# Main.net
KiCad netlist of a schematic drawn in Altium Designer
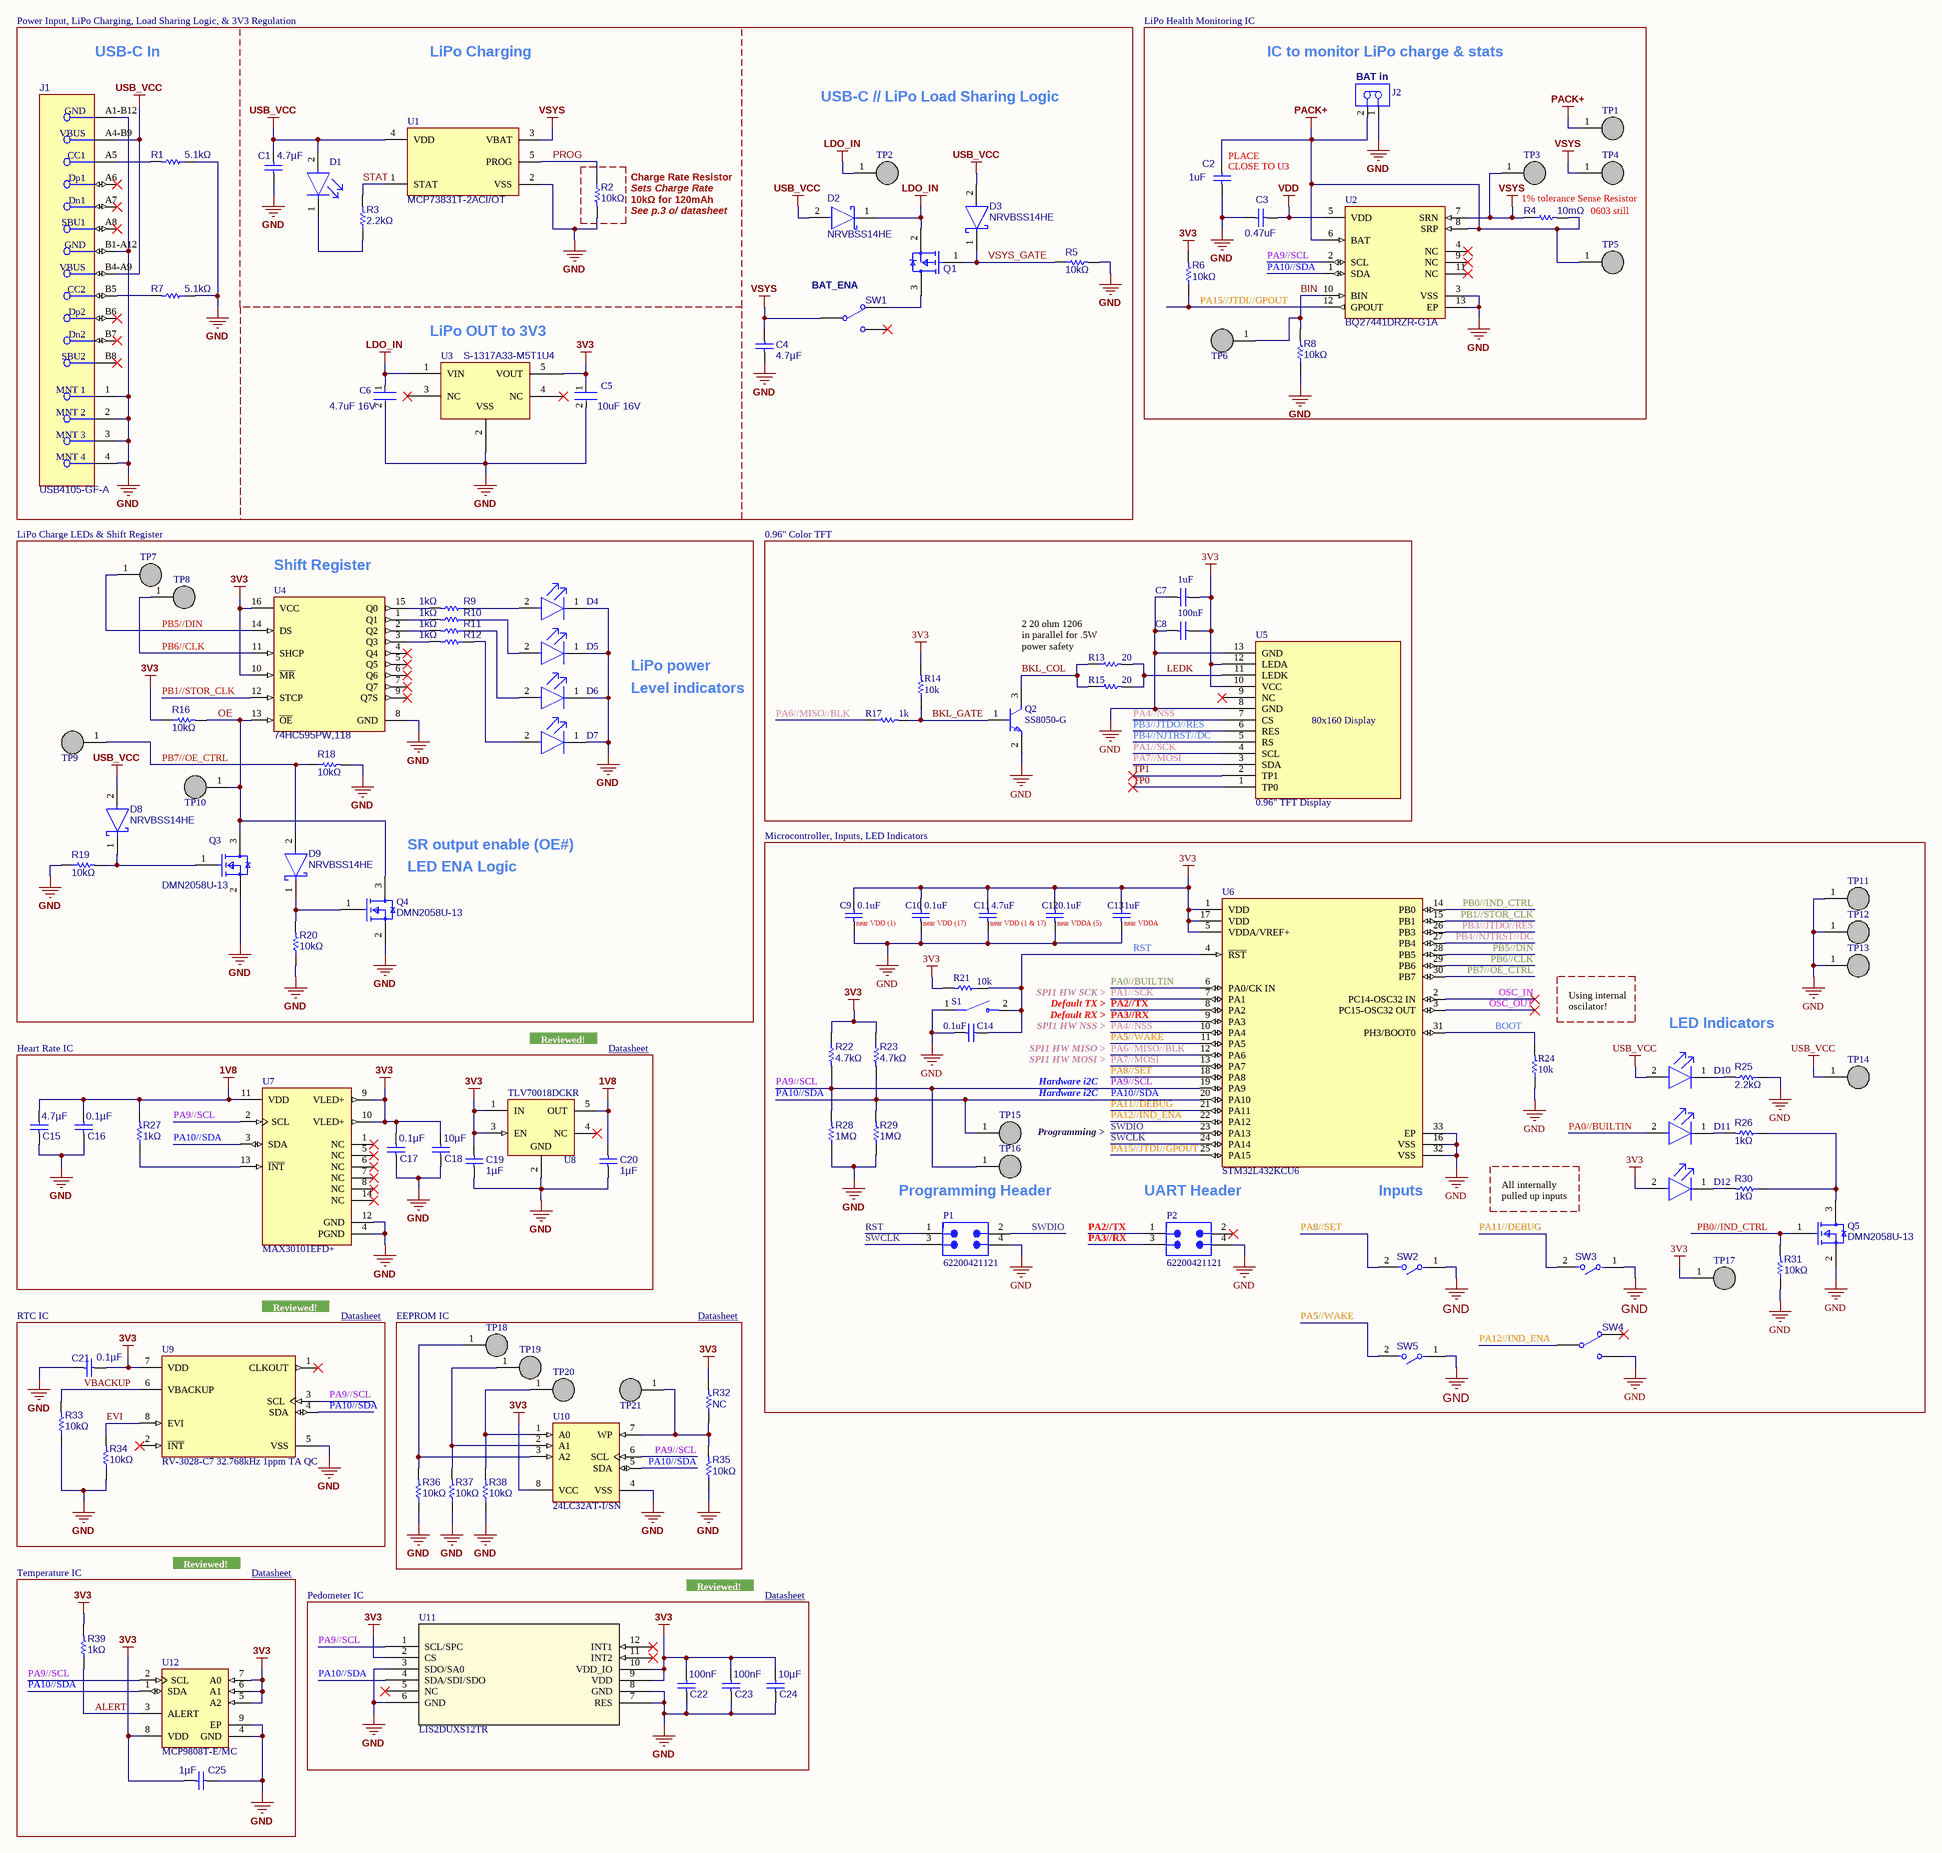
[diagram p0: Main.SchDoc]

(export (version "E")
  (design (tool "Eeschema 10.0.6"))
  (components
    (comp (ref "C1")
      (value "4.7µF")
      (footprint "WCAP-CSGP_0603_L1.6W0.8H0.8_Reflow")
      (libsource (lib "Altium Content Vault") (part "Capacitor_Non-Polarized"))
    )
    (comp (ref "C2")
      (value "1uF")
      (footprint "WCAP-CSGP_0603_L1.6W0.8H0.8_Reflow")
      (libsource (lib "Altium Content Vault") (part "Capacitor_Non-Polarized"))
    )
    (comp (ref "C3")
      (value "0.47uF")
      (footprint "WCAP-CSGP_0603_L1.6W0.8H0.8_Reflow")
      (libsource (lib "Altium Content Vault") (part "Capacitor_Non-Polarized"))
    )
    (comp (ref "C4")
      (value "4.7µF")
      (footprint "WCAP-CSGP_0603_L1.6W0.8H0.8_Reflow")
      (libsource (lib "Altium Content Vault") (part "Capacitor_Non-Polarized"))
    )
    (comp (ref "C5")
      (value "10uF 16V")
      (footprint "FP-CC0603-DC-MFG")
      (description "CM105X5R106K16AT")
      (fields (field (name "TOLERANCE") "10%"))
      (libsource (lib "Altium Content Vault") (part "b4654b650e69147ec39a6b967a45e02"))
    )
    (comp (ref "C6")
      (value "4.7uF 16V")
      (footprint "FP-CC0603-DA-MFG")
      (description "GRM188Z71C475KE21D")
      (fields
        (field (name "MANUFACTURER") "YAGEO")
        (field (name "MANUFACTURER PART NUMBER") "CC0603KRX5R7BB475")
      )
      (libsource (lib "Altium Content Vault") (part "11868f565c42a9108669ba33697ecf6"))
    )
    (comp (ref "C7")
      (value "1uF")
      (footprint "CAPC1608X87X35NL15T15")
      (libsource (lib "Altium Content Vault") (part "CAP"))
    )
    (comp (ref "C8")
      (value "100nF")
      (footprint "CAPC1608X87X35NL15T15")
      (libsource (lib "Altium Content Vault") (part "CAP"))
    )
    (comp (ref "C9")
      (value "0.1uF")
      (footprint "CAPC1608X87X35NL15T15")
      (libsource (lib "Altium Content Vault") (part "CAP"))
    )
    (comp (ref "C10")
      (value "0.1uF")
      (footprint "CAPC1608X87X35NL15T15")
      (libsource (lib "Altium Content Vault") (part "CAP"))
    )
    (comp (ref "C11")
      (value "4.7uF")
      (footprint "CAPC1608X87X35NL15T15")
      (libsource (lib "Altium Content Vault") (part "CAP"))
    )
    (comp (ref "C12")
      (value "0.1uF")
      (footprint "CAPC1608X87X35NL15T15")
      (libsource (lib "Altium Content Vault") (part "CAP"))
    )
    (comp (ref "C13")
      (value "1uF")
      (footprint "CAPC1608X87X35NL15T15")
      (libsource (lib "Altium Content Vault") (part "CAP"))
    )
    (comp (ref "C14")
      (value "0.1uF")
      (footprint "CAPC1608X87X35NL15T15")
      (libsource (lib "Altium Content Vault") (part "CAP"))
    )
    (comp (ref "C15")
      (value "4.7µF")
      (footprint "WCAP-CSGP_0603_L1.6W0.8H0.8_Reflow")
      (description "10V tolerance")
      (libsource (lib "Altium Content Vault") (part "Capacitor_Non-Polarized"))
    )
    (comp (ref "C16")
      (value "0.1µF")
      (footprint "WCAP-CSGP_0603_L1.6W0.8H0.8_Reflow")
      (description "10V tolerance")
      (libsource (lib "Altium Content Vault") (part "Capacitor_Non-Polarized"))
    )
    (comp (ref "C17")
      (value "0.1µF")
      (footprint "WCAP-CSGP_0603_L1.6W0.8H0.8_Reflow")
      (description "10V tolerance")
      (libsource (lib "Altium Content Vault") (part "Capacitor_Non-Polarized"))
    )
    (comp (ref "C18")
      (value "10µF")
      (footprint "WCAP-CSGP_0603_L1.6W0.8H0.8_Reflow")
      (description "10V tolerance")
      (libsource (lib "Altium Content Vault") (part "Capacitor_Non-Polarized"))
    )
    (comp (ref "C19")
      (value "1µF")
      (footprint "WCAP-CSGP_0603_L1.6W0.8H0.8_Reflow")
      (description "10V tolerance")
      (libsource (lib "Altium Content Vault") (part "Capacitor_Non-Polarized"))
    )
    (comp (ref "C20")
      (value "1µF")
      (footprint "WCAP-CSGP_0603_L1.6W0.8H0.8_Reflow")
      (description "10V tolerance")
      (libsource (lib "Altium Content Vault") (part "Capacitor_Non-Polarized"))
    )
    (comp (ref "C21")
      (value "0.1µF")
      (footprint "WCAP-CSGP_0603_L1.6W0.8H0.8_Reflow")
      (description "10V tolerance")
      (libsource (lib "Altium Content Vault") (part "Capacitor_Non-Polarized"))
    )
    (comp (ref "C22")
      (value "100nF")
      (footprint "WCAP-CSGP_0603_L1.6W0.8H0.8_Reflow")
      (description "10V tolerance")
      (libsource (lib "Altium Content Vault") (part "Capacitor_Non-Polarized"))
    )
    (comp (ref "C23")
      (value "100nF")
      (footprint "WCAP-CSGP_0603_L1.6W0.8H0.8_Reflow")
      (description "10V tolerance")
      (libsource (lib "Altium Content Vault") (part "Capacitor_Non-Polarized"))
    )
    (comp (ref "C24")
      (value "10µF")
      (footprint "WCAP-CSGP_0603_L1.6W0.8H0.8_Reflow")
      (description "10V tolerance")
      (libsource (lib "Altium Content Vault") (part "Capacitor_Non-Polarized"))
    )
    (comp (ref "C25")
      (value "1µF")
      (footprint "WCAP-CSGP_0603_L1.6W0.8H0.8_Reflow")
      (description "10V tolerance")
      (libsource (lib "Altium Content Vault") (part "Capacitor_Non-Polarized"))
    )
    (comp (ref "D1")
      (value "LTST-C190KGKT")
      (footprint "FP-LTST-C190KGKT-MFG")
      (description "LED GREEN CLEAR CHIP SMD")
      (libsource (lib "Altium Content Vault") (part "8706943c75ba83719d021d2fdc84c58"))
    )
    (comp (ref "D2")
      (value "NRVBSS14HE")
      (footprint "FP-477AD-MFG")
      (description "NRVBSS14HE Rectifier Diode, Schottky, 1 Phase, 1 Element, 1A, 40V V(RRM), Silicon")
      (libsource (lib "Altium Content Vault") (part "c1678fac7984e62e0809fbf79c06691"))
    )
    (comp (ref "D3")
      (value "NRVBSS14HE")
      (footprint "FP-477AD-MFG")
      (description "NRVBSS14HE Rectifier Diode, Schottky, 1 Phase, 1 Element, 1A, 40V V(RRM), Silicon")
      (libsource (lib "Altium Content Vault") (part "c1678fac7984e62e0809fbf79c06691"))
    )
    (comp (ref "D4")
      (value "LTST-C190KGKT")
      (footprint "FP-LTST-C190KGKT-MFG")
      (description "LED GREEN CLEAR CHIP SMD")
      (libsource (lib "Altium Content Vault") (part "8706943c75ba83719d021d2fdc84c58"))
    )
    (comp (ref "D5")
      (value "LTST-C190KGKT")
      (footprint "FP-LTST-C190KGKT-MFG")
      (description "LED GREEN CLEAR CHIP SMD")
      (libsource (lib "Altium Content Vault") (part "8706943c75ba83719d021d2fdc84c58"))
    )
    (comp (ref "D6")
      (value "LTST-C190KGKT")
      (footprint "FP-LTST-C190KGKT-MFG")
      (description "LED GREEN CLEAR CHIP SMD")
      (libsource (lib "Altium Content Vault") (part "8706943c75ba83719d021d2fdc84c58"))
    )
    (comp (ref "D7")
      (value "LTST-C190KGKT")
      (footprint "FP-LTST-C190KGKT-MFG")
      (description "LED GREEN CLEAR CHIP SMD")
      (libsource (lib "Altium Content Vault") (part "8706943c75ba83719d021d2fdc84c58"))
    )
    (comp (ref "D8")
      (value "NRVBSS14HE")
      (footprint "FP-477AD-MFG")
      (description "NRVBSS14HE Rectifier Diode, Schottky, 1 Phase, 1 Element, 1A, 40V V(RRM), Silicon")
      (libsource (lib "Altium Content Vault") (part "c1678fac7984e62e0809fbf79c06691"))
    )
    (comp (ref "D9")
      (value "NRVBSS14HE")
      (footprint "FP-477AD-MFG")
      (description "NRVBSS14HE Rectifier Diode, Schottky, 1 Phase, 1 Element, 1A, 40V V(RRM), Silicon")
      (libsource (lib "Altium Content Vault") (part "c1678fac7984e62e0809fbf79c06691"))
    )
    (comp (ref "D10")
      (value "LTST-C190KGKT")
      (footprint "FP-LTST-C190KGKT-MFG")
      (description "LED GREEN CLEAR CHIP SMD")
      (libsource (lib "Altium Content Vault") (part "8706943c75ba83719d021d2fdc84c58"))
    )
    (comp (ref "D11")
      (value "LTST-C190KGKT")
      (footprint "FP-LTST-C190KGKT-MFG")
      (description "LED GREEN CLEAR CHIP SMD")
      (libsource (lib "Altium Content Vault") (part "8706943c75ba83719d021d2fdc84c58"))
    )
    (comp (ref "D12")
      (value "LTST-C190KGKT")
      (footprint "FP-LTST-C190KGKT-MFG")
      (description "LED GREEN CLEAR CHIP SMD")
      (libsource (lib "Altium Content Vault") (part "8706943c75ba83719d021d2fdc84c58"))
    )
    (comp (ref "J1")
      (value "USB4105-GF-A")
      (footprint "FP-USB4105-GF-A-MFG")
      (description "CONN RCPT USB2.0 TYPEC 5A")
      (fields
        (field (name "MANUFACTURER") "GCT")
        (field (name "OCTOPART") "https://octopart.com/usb4105-gf-a-gct-106627878")
      )
      (libsource (lib "Altium Content Vault") (part "e7c17a616881a82b79941196b4bec10"))
    )
    (comp (ref "J2")
      (value "B2B-PH-K-S(LF)(SN)")
      (footprint "JST-B2B-PH-K-S_V")
      (fields (field (name "MANUFACTURER") "JST"))
      (libsource (lib "Altium Content Vault") (part "CN-2P-F-QF2"))
    )
    (comp (ref "P1")
      (value "62200421121")
      (footprint "62200421121")
      (description "THT Vertical Pin Header WR-PHD, Pitch 1.27 mm, Dual Row, 4 pins")
      (libsource (lib "Altium Content Vault") (part "Header_Male_2R_04P"))
    )
    (comp (ref "P2")
      (value "62200421121")
      (footprint "62200421121")
      (description "THT Vertical Pin Header WR-PHD, Pitch 1.27 mm, Dual Row, 4 pins")
      (libsource (lib "Altium Content Vault") (part "Header_Male_2R_04P"))
    )
    (comp (ref "Q1")
      (value "IRLML6402TRPBF")
      (footprint "FP-Micro3-MFG")
      (description "MOSFET P-CH 20V 3.7A SOT-23")
      (fields
        (field (name "OCTOPART") "https://octopart.com/irlml6402trpbf-infineon-65874989")
        (field (name "MANUFACTURER") "Infineon")
      )
      (libsource (lib "Altium Content Vault") (part "566027c8dc92b5207d53ac25ab3eb60"))
    )
    (comp (ref "Q2")
      (value "SS8050-G")
      (footprint "FP-SS8050-G-MFG")
      (description "NPN TRANSISTOR 1.5A 40V SOT-23 R")
      (libsource (lib "Altium Content Vault") (part "2a1388f82443b098dcd57d24ac7632d"))
    )
    (comp (ref "Q3")
      (value "DMN2058U-13")
      (footprint "FP-C04-17458-MFG")
      (description "TN2130K1-G Mosfet, N-Channel Enhancement-Mode, 300V, 25 Ohm Rohs Compliant: Yes")
      (libsource (lib "Altium Content Vault") (part "3b9c635fedb024a5347a57b145af9cc"))
    )
    (comp (ref "Q4")
      (value "DMN2058U-13")
      (footprint "FP-C04-17458-MFG")
      (description "TN2130K1-G Mosfet, N-Channel Enhancement-Mode, 300V, 25 Ohm Rohs Compliant: Yes")
      (libsource (lib "Altium Content Vault") (part "3b9c635fedb024a5347a57b145af9cc"))
    )
    (comp (ref "Q5")
      (value "DMN2058U-13")
      (footprint "FP-C04-17458-MFG")
      (description "TN2130K1-G Mosfet, N-Channel Enhancement-Mode, 300V, 25 Ohm Rohs Compliant: Yes")
      (libsource (lib "Altium Content Vault") (part "3b9c635fedb024a5347a57b145af9cc"))
    )
    (comp (ref "R1")
      (value "5.1kΩ")
      (footprint "RESC1608X55X25NL10T15")
      (libsource (lib "Altium Content Vault") (part "RES"))
    )
    (comp (ref "R2")
      (value "10kΩ")
      (footprint "RESC1608X55X25NL10T15")
      (libsource (lib "Altium Content Vault") (part "RES"))
    )
    (comp (ref "R3")
      (value "2.2kΩ")
      (footprint "RESC1608X55X25NL10T15")
      (libsource (lib "Altium Content Vault") (part "RES"))
    )
    (comp (ref "R4")
      (value "10mΩ")
      (footprint "RESC1608X55X25NL10T15")
      (libsource (lib "Altium Content Vault") (part "RES"))
    )
    (comp (ref "R5")
      (value "10kΩ")
      (footprint "RESC1608X55X25NL10T15")
      (libsource (lib "Altium Content Vault") (part "RES"))
    )
    (comp (ref "R6")
      (value "10kΩ")
      (footprint "RESC1608X55X25NL10T15")
      (libsource (lib "Altium Content Vault") (part "RES"))
    )
    (comp (ref "R7")
      (value "5.1kΩ")
      (footprint "RESC1608X55X25NL10T15")
      (libsource (lib "Altium Content Vault") (part "RES"))
    )
    (comp (ref "R8")
      (value "10kΩ")
      (footprint "RESC1608X55X25NL10T15")
      (libsource (lib "Altium Content Vault") (part "RES"))
    )
    (comp (ref "R9")
      (value "1kΩ")
      (footprint "RESC1608X55X25NL10T15")
      (libsource (lib "Altium Content Vault") (part "RES"))
    )
    (comp (ref "R10")
      (value "1kΩ")
      (footprint "RESC1608X55X25NL10T15")
      (libsource (lib "Altium Content Vault") (part "RES"))
    )
    (comp (ref "R11")
      (value "1kΩ")
      (footprint "RESC1608X55X25NL10T15")
      (libsource (lib "Altium Content Vault") (part "RES"))
    )
    (comp (ref "R12")
      (value "1kΩ")
      (footprint "RESC1608X55X25NL10T15")
      (libsource (lib "Altium Content Vault") (part "RES"))
    )
    (comp (ref "R13")
      (value "20")
      (footprint "RESC3116X65X40NL10T20")
      (fields (field (name "MANUFACTURER") "Yageo") (field (name "PART NUMBER") "RC1206JR-0720RL"))
      (libsource (lib "Altium Content Vault") (part "RES"))
    )
    (comp (ref "R14")
      (value "10k")
      (footprint "RESC1608X55X25NL10T15")
      (fields (field (name "PART NUMBER") "RT0603BRE071KL") (field (name "MANUFACTURER") "Yageo"))
      (libsource (lib "Altium Content Vault") (part "RES"))
    )
    (comp (ref "R15")
      (value "20")
      (footprint "RESC3116X65X40NL10T20")
      (fields (field (name "MANUFACTURER") "Yageo") (field (name "PART NUMBER") "RC1206JR-0720RL"))
      (libsource (lib "Altium Content Vault") (part "RES"))
    )
    (comp (ref "R16")
      (value "10kΩ")
      (footprint "RESC1608X55X25NL10T15")
      (libsource (lib "Altium Content Vault") (part "RES"))
    )
    (comp (ref "R17")
      (value "1k")
      (footprint "RESC1608X55X25NL10T15")
      (fields (field (name "PART NUMBER") "RT0603BRE071KL") (field (name "MANUFACTURER") "Yageo"))
      (libsource (lib "Altium Content Vault") (part "RES"))
    )
    (comp (ref "R18")
      (value "10kΩ")
      (footprint "RESC1608X55X25NL10T15")
      (libsource (lib "Altium Content Vault") (part "RES"))
    )
    (comp (ref "R19")
      (value "10kΩ")
      (footprint "RESC1608X55X25NL10T15")
      (libsource (lib "Altium Content Vault") (part "RES"))
    )
    (comp (ref "R20")
      (value "10kΩ")
      (footprint "RESC1608X55X25NL10T15")
      (libsource (lib "Altium Content Vault") (part "RES"))
    )
    (comp (ref "R21")
      (value "10k")
      (footprint "RESC1608X55X25NL10T15")
      (fields (field (name "PART NUMBER") "RT0603BRE071KL") (field (name "MANUFACTURER") "Yageo"))
      (libsource (lib "Altium Content Vault") (part "RES"))
    )
    (comp (ref "R22")
      (value "4.7kΩ")
      (footprint "RESC1608X55X25NL10T15")
      (libsource (lib "Altium Content Vault") (part "RES"))
    )
    (comp (ref "R23")
      (value "4.7kΩ")
      (footprint "RESC1608X55X25NL10T15")
      (libsource (lib "Altium Content Vault") (part "RES"))
    )
    (comp (ref "R24")
      (value "10k")
      (footprint "RESC1608X55X25NL10T15")
      (fields (field (name "PART NUMBER") "RT0603BRE071KL") (field (name "MANUFACTURER") "Yageo"))
      (libsource (lib "Altium Content Vault") (part "RES"))
    )
    (comp (ref "R25")
      (value "2.2kΩ")
      (footprint "RESC1608X55X25NL10T15")
      (libsource (lib "Altium Content Vault") (part "RES"))
    )
    (comp (ref "R26")
      (value "1kΩ")
      (footprint "RESC1608X55X25NL10T15")
      (libsource (lib "Altium Content Vault") (part "RES"))
    )
    (comp (ref "R27")
      (value "1kΩ")
      (footprint "RESC1608X55X25NL10T15")
      (libsource (lib "Altium Content Vault") (part "RES"))
    )
    (comp (ref "R28")
      (value "1MΩ")
      (footprint "RESC1608X55X25NL10T15")
      (libsource (lib "Altium Content Vault") (part "RES"))
    )
    (comp (ref "R29")
      (value "1MΩ")
      (footprint "RESC1608X55X25NL10T15")
      (libsource (lib "Altium Content Vault") (part "RES"))
    )
    (comp (ref "R30")
      (value "1kΩ")
      (footprint "RESC1608X55X25NL10T15")
      (libsource (lib "Altium Content Vault") (part "RES"))
    )
    (comp (ref "R31")
      (value "10kΩ")
      (footprint "RESC1608X55X25NL10T15")
      (libsource (lib "Altium Content Vault") (part "RES"))
    )
    (comp (ref "R32")
      (value "NC")
      (footprint "RESC1608X55X25NL10T15")
      (libsource (lib "Altium Content Vault") (part "RES"))
    )
    (comp (ref "R33")
      (value "10kΩ")
      (footprint "RESC1608X55X25NL10T15")
      (libsource (lib "Altium Content Vault") (part "RES"))
    )
    (comp (ref "R34")
      (value "10kΩ")
      (footprint "RESC1608X55X25NL10T15")
      (libsource (lib "Altium Content Vault") (part "RES"))
    )
    (comp (ref "R35")
      (value "10kΩ")
      (footprint "RESC1608X55X25NL10T15")
      (libsource (lib "Altium Content Vault") (part "RES"))
    )
    (comp (ref "R36")
      (value "10kΩ")
      (footprint "RESC1608X55X25NL10T15")
      (libsource (lib "Altium Content Vault") (part "RES"))
    )
    (comp (ref "R37")
      (value "10kΩ")
      (footprint "RESC1608X55X25NL10T15")
      (libsource (lib "Altium Content Vault") (part "RES"))
    )
    (comp (ref "R38")
      (value "10kΩ")
      (footprint "RESC1608X55X25NL10T15")
      (libsource (lib "Altium Content Vault") (part "RES"))
    )
    (comp (ref "R39")
      (value "1kΩ")
      (footprint "RESC1608X55X25NL10T15")
      (libsource (lib "Altium Content Vault") (part "RES"))
    )
    (comp (ref "S1")
      (value "TS09-63-25-WT-260-SMT-TR")
      (footprint "SW_TS09-63-25-WT-260-SMT-TR")
      (description "6.1 x 3.7 mm, 2.5 mm Actuator Height, 260 gf, White, Surface Mount, SPST, Tactile Switch")
      (fields (field (name "MF") "Same Sky"))
      (libsource (lib "TS09-63-25-WT-260-SMT-TR") (part "TS09-63-25-WT-260-SMT-TR"))
    )
    (comp (ref "SW1")
      (value "450404015514")
      (footprint "450404015514")
      (description "450404015514 Slide Switch, 0.3A, 5Vdc, Smd Rohs Compliant: Yes")
      (libsource (lib "Altium Content Vault") (part "SPDT"))
    )
    (comp (ref "SW2")
      (value "RST")
      (footprint "FP-B3U-1000P-B-MFG")
      (description "SWITCH TACTILE SPST-NO 0.05A 12V")
      (fields
        (field (name "MANUFACTURER PART NUMBER") "B3U-1000P-B")
        (field (name "OCTOPART") "https://octopart.com/b3u-1000p-b-omron-1057356")
      )
      (libsource (lib "Altium Content Vault") (part "bb27bde45df87f1f469753f287ef5ae"))
    )
    (comp (ref "SW3")
      (value "RST")
      (footprint "FP-B3U-1000P-B-MFG")
      (description "SWITCH TACTILE SPST-NO 0.05A 12V")
      (fields
        (field (name "MANUFACTURER PART NUMBER") "B3U-1000P-B")
        (field (name "OCTOPART") "https://octopart.com/b3u-1000p-b-omron-1057356")
      )
      (libsource (lib "Altium Content Vault") (part "bb27bde45df87f1f469753f287ef5ae"))
    )
    (comp (ref "SW4")
      (value "450404015514")
      (footprint "450404015514")
      (description "450404015514 Slide Switch, 0.3A, 5Vdc, Smd Rohs Compliant: Yes")
      (libsource (lib "Altium Content Vault") (part "SPDT"))
    )
    (comp (ref "SW5")
      (value "RST")
      (footprint "FP-B3U-1000P-B-MFG")
      (description "SWITCH TACTILE SPST-NO 0.05A 12V")
      (fields
        (field (name "MANUFACTURER PART NUMBER") "B3U-1000P-B")
        (field (name "OCTOPART") "https://octopart.com/b3u-1000p-b-omron-1057356")
      )
      (libsource (lib "Altium Content Vault") (part "bb27bde45df87f1f469753f287ef5ae"))
    )
    (comp (ref "TP1")
      (value "Testpoint")
      (footprint "Testpoint Footprint")
      (libsource (lib "DebuggingLib") (part "Testpoint"))
    )
    (comp (ref "TP2")
      (value "Testpoint")
      (footprint "Testpoint Footprint")
      (libsource (lib "DebuggingLib") (part "Testpoint"))
    )
    (comp (ref "TP3")
      (value "Testpoint")
      (footprint "Testpoint Footprint")
      (libsource (lib "DebuggingLib") (part "Testpoint"))
    )
    (comp (ref "TP4")
      (value "Testpoint")
      (footprint "Testpoint Footprint")
      (libsource (lib "DebuggingLib") (part "Testpoint"))
    )
    (comp (ref "TP5")
      (value "Testpoint")
      (footprint "Testpoint Footprint")
      (libsource (lib "DebuggingLib") (part "Testpoint"))
    )
    (comp (ref "TP6")
      (value "Testpoint")
      (footprint "Testpoint Footprint")
      (libsource (lib "DebuggingLib") (part "Testpoint"))
    )
    (comp (ref "TP7")
      (value "Testpoint")
      (footprint "Testpoint Footprint")
      (libsource (lib "DebuggingLib") (part "Testpoint"))
    )
    (comp (ref "TP8")
      (value "Testpoint")
      (footprint "Testpoint Footprint")
      (libsource (lib "DebuggingLib") (part "Testpoint"))
    )
    (comp (ref "TP9")
      (value "Testpoint")
      (footprint "Testpoint Footprint")
      (libsource (lib "DebuggingLib") (part "Testpoint"))
    )
    (comp (ref "TP10")
      (value "Testpoint")
      (footprint "Testpoint Footprint")
      (libsource (lib "DebuggingLib") (part "Testpoint"))
    )
    (comp (ref "TP11")
      (value "Testpoint")
      (footprint "Testpoint Footprint")
      (libsource (lib "DebuggingLib") (part "Testpoint"))
    )
    (comp (ref "TP12")
      (value "Testpoint")
      (footprint "Testpoint Footprint")
      (libsource (lib "DebuggingLib") (part "Testpoint"))
    )
    (comp (ref "TP13")
      (value "Testpoint")
      (footprint "Testpoint Footprint")
      (libsource (lib "DebuggingLib") (part "Testpoint"))
    )
    (comp (ref "TP14")
      (value "Testpoint")
      (footprint "Testpoint Footprint")
      (libsource (lib "DebuggingLib") (part "Testpoint"))
    )
    (comp (ref "TP15")
      (value "Testpoint")
      (footprint "Testpoint Footprint")
      (libsource (lib "DebuggingLib") (part "Testpoint"))
    )
    (comp (ref "TP16")
      (value "Testpoint")
      (footprint "Testpoint Footprint")
      (libsource (lib "DebuggingLib") (part "Testpoint"))
    )
    (comp (ref "TP17")
      (value "Testpoint")
      (footprint "Testpoint Footprint")
      (libsource (lib "DebuggingLib") (part "Testpoint"))
    )
    (comp (ref "TP18")
      (value "Testpoint")
      (footprint "Testpoint Footprint")
      (libsource (lib "DebuggingLib") (part "Testpoint"))
    )
    (comp (ref "TP19")
      (value "Testpoint")
      (footprint "Testpoint Footprint")
      (libsource (lib "DebuggingLib") (part "Testpoint"))
    )
    (comp (ref "TP20")
      (value "Testpoint")
      (footprint "Testpoint Footprint")
      (libsource (lib "DebuggingLib") (part "Testpoint"))
    )
    (comp (ref "TP21")
      (value "Testpoint")
      (footprint "Testpoint Footprint")
      (libsource (lib "DebuggingLib") (part "Testpoint"))
    )
    (comp (ref "U1")
      (value "MCP73831T-2ACI/OT")
      (footprint "FP-C04-091-OT-MFG")
      (description "IC CONTROLLR LI-ION 4.2V SOT23-5")
      (libsource (lib "Altium Content Vault") (part "61f5a3bb3429d9e0caadea342aa3b19"))
    )
    (comp (ref "U2")
      (value "BQ27441DRZR-G1A")
      (footprint "FP-DRZ0012A-MFG")
      (description "IC BATT FUEL GAUGE LI-ION 12SON")
      (fields
        (field (name "OCTOPART") "https://octopart.com/bq27441drzr-g1a-texas+instruments-30555829")
        (field (name "MANUFACTURER") "Texas Instruments")
      )
      (libsource (lib "Altium Content Vault") (part "0f562f18464a1f07b55dcd927f1fdf2"))
    )
    (comp (ref "U3")
      (value "S-1317A33-M5T1U4")
      (footprint "S-1317A33-M5T1U4")
      (libsource (lib "1317A33-M5T1U4") (part "S-1317A33-M5T1U4"))
    )
    (comp (ref "U4")
      (value "74HC595PW,118")
      (footprint "FP-SOT403-1-MFG")
      (description "IC SHIFT REGISTER 8BIT 16TSSOP")
      (libsource (lib "Altium Content Vault") (part "27683e23285b137cd268a0f18c66bed"))
    )
    (comp (ref "U5")
      (value "0.96\" TFT Display")
      (footprint "PCBComponent_1")
      (libsource (lib "disp_0.96") (part "0.96{dblquote} TFT Display"))
    )
    (comp (ref "U6")
      (value "STM32L432KCU6")
      (footprint "FP-UFQFPN32-A0B8-MFG")
      (description "IC MCU 32BIT 256KB FLASH 32QFPN")
      (fields
        (field (name "OCTOPART") "https://octopart.com/stm32l432kcu6-stmicroelectronics-71093510")
        (field (name "MANUFACTURER") "STMicroelectronics")
      )
      (libsource (lib "Altium Content Vault") (part "f3240dca552e0aa49c1b4baba198c12"))
    )
    (comp (ref "U7")
      (value "MAX30101EFD+")
      (footprint "FP-F143A5-1-MFG")
      (description "INTEGRATED OPTICAL SENSOR")
      (fields
        (field (name "MANUFACTURER") "Maxim Integrated")
        (field (name "OCTOPART") "https://octopart.com/max30101efd%2B-maxim+integrated-57054333")
      )
      (libsource (lib "Altium Content Vault") (part "7412f82398c18c21c59cad441ae59a4"))
    )
    (comp (ref "U8")
      (value "TLV70018DCKR")
      (footprint "DCK0005A_L")
      (fields (field (name "MANUFACTURER") "Texas Instruments"))
      (libsource (lib "Altium Content Vault") (part "TI-TXX7XXXX-5"))
    )
    (comp (ref "U9")
      (value "RV-3028-C7 32.768kHz 1ppm TA QC")
      (footprint "FP-RV-3028-C7_32_768kHz_1-MFG")
      (description "Real Time Clock Serial 2byte Clock/Calendar/Alarm/Timer/Battery Backup 8-Pin CSMD T/R")
      (fields
        (field (name "OCTOPART") "https://octopart.com/rv-3028-c7+32.768khz+1ppm+ta+qc-micro+crystal-98880451")
        (field (name "MANUFACTURER") "Micro Crystal")
      )
      (libsource (lib "Altium Content Vault") (part "f06799675b941e5ee1fb77ef065374c"))
    )
    (comp (ref "U10")
      (value "24LC32AT-I/SN")
      (footprint "SOIC-SN8_M")
      (description "32Kbit, 400kHz, 2.5V, I2C Serial EEPROM, 8-Pin SOIC 150mil, Industrial Temperature, Tape and Reel")
      (libsource (lib "Altium Content Vault") (part "MEM-SEEPROM-34AA02-IL8"))
    )
    (comp (ref "U11")
      (value "LIS2DUXS12TR")
      (footprint "QFN_DUXS12_STM")
      (fields (field (name "COPYRIGHT") "Copyright (C) 2025 Ultra Librarian. All rights reserved."))
      (libsource (lib "LIS2DUXS12TR") (part "LIS2DUXS12TR"))
    )
    (comp (ref "U12")
      (value "MCP9808T-E/MC")
      (footprint "MCHP-DFN-MC8_V")
      (fields (field (name "MANUFACTURER") "Microchip"))
      (libsource (lib "Altium Content Vault") (part "MCHP-MCP9808-DFN-8"))
    )
  )
  (nets
    (net (code "1") (name "/ALERT") (class "Default")
      (node (ref "R39") (pin "1") (pinfunction "1_1") (pintype "passive"))
      (node (ref "U12") (pin "3") (pinfunction "ALERT_3") (pintype "open_collector"))
    )
    (net (code "2") (name "/BIN") (class "Default")
      (node (ref "R8") (pin "2") (pinfunction "2_2") (pintype "passive"))
      (node (ref "TP6") (pin "1") (pintype "passive"))
      (node (ref "U2") (pin "10") (pinfunction "BIN_10") (pintype "input"))
    )
    (net (code "3") (name "/BKL_COL") (class "Default")
      (node (ref "Q2") (pin "3") (pinfunction "C_3") (pintype "passive"))
      (node (ref "R13") (pin "1") (pinfunction "1_1") (pintype "passive"))
      (node (ref "R15") (pin "1") (pinfunction "1_1") (pintype "passive"))
    )
    (net (code "4") (name "/BKL_GATE") (class "Default")
      (node (ref "Q2") (pin "1") (pinfunction "B_1") (pintype "passive"))
      (node (ref "R14") (pin "1") (pinfunction "1_1") (pintype "passive"))
      (node (ref "R17") (pin "2") (pinfunction "2_2") (pintype "passive"))
    )
    (net (code "5") (name "/BOOT") (class "Default")
      (node (ref "R24") (pin "2") (pinfunction "2_2") (pintype "passive"))
      (node (ref "U6") (pin "31") (pinfunction "PH3/BOOT0_31") (pintype "bidirectional"))
    )
    (net (code "6") (name "/EVI") (class "Default")
      (node (ref "R34") (pin "2") (pinfunction "2_2") (pintype "passive"))
      (node (ref "U9") (pin "8") (pinfunction "EVI_8") (pintype "input"))
    )
    (net (code "7") (name "/LEDK") (class "Default")
      (node (ref "R13") (pin "2") (pinfunction "2_2") (pintype "passive"))
      (node (ref "R15") (pin "2") (pinfunction "2_2") (pintype "passive"))
      (node (ref "U5") (pin "11") (pinfunction "LEDK_11") (pintype "passive"))
    )
    (net (code "8") (name "/OE") (class "Default")
      (node (ref "Q3") (pin "3") (pinfunction "D_3") (pintype "passive"))
      (node (ref "Q4") (pin "3") (pinfunction "D_3") (pintype "passive"))
      (node (ref "R16") (pin "2") (pinfunction "2_2") (pintype "passive"))
      (node (ref "TP10") (pin "1") (pintype "passive"))
      (node (ref "U4") (pin "13") (pinfunction "~{OE}_13") (pintype "input"))
    )
    (net (code "9") (name "/OSC_IN") (class "Default")
      (node (ref "U6") (pin "2") (pinfunction "PC14-OSC32_IN_2") (pintype "bidirectional+no_connect"))
    )
    (net (code "10") (name "/OSC_OUT") (class "Default")
      (node (ref "U6") (pin "3") (pinfunction "PC15-OSC32_OUT_3") (pintype "bidirectional+no_connect"))
    )
    (net (code "11") (name "/PA0{slash}{slash}BUILTIN") (class "Default")
      (node (ref "D11") (pin "2") (pinfunction "A_2") (pintype "passive"))
      (node (ref "U6") (pin "6") (pinfunction "PA0/CK_IN_6") (pintype "bidirectional"))
    )
    (net (code "12") (name "/PA1{slash}{slash}SCK") (class "Default")
      (node (ref "U5") (pin "4") (pinfunction "SCL_4") (pintype "passive"))
      (node (ref "U6") (pin "7") (pinfunction "PA1_7") (pintype "bidirectional"))
    )
    (net (code "13") (name "/PA2{slash}{slash}TX") (class "Default")
      (node (ref "P2") (pin "1") (pinfunction "1_1") (pintype "passive"))
      (node (ref "U6") (pin "8") (pinfunction "PA2_8") (pintype "bidirectional"))
    )
    (net (code "14") (name "/PA3{slash}{slash}RX") (class "Default")
      (node (ref "P2") (pin "3") (pinfunction "3_3") (pintype "passive"))
      (node (ref "U6") (pin "9") (pinfunction "PA3_9") (pintype "bidirectional"))
    )
    (net (code "15") (name "/PA4{slash}{slash}NSS") (class "Default")
      (node (ref "U5") (pin "7") (pinfunction "CS_7") (pintype "passive"))
      (node (ref "U6") (pin "10") (pinfunction "PA4_10") (pintype "bidirectional"))
    )
    (net (code "16") (name "/PA5{slash}{slash}WAKE") (class "Default")
      (node (ref "SW5") (pin "2") (pinfunction "2_2") (pintype "passive"))
      (node (ref "U6") (pin "11") (pinfunction "PA5_11") (pintype "bidirectional"))
    )
    (net (code "17") (name "/PA6{slash}{slash}MISO{slash}{slash}BLK") (class "Default")
      (node (ref "R17") (pin "1") (pinfunction "1_1") (pintype "passive"))
      (node (ref "U6") (pin "12") (pinfunction "PA6_12") (pintype "bidirectional"))
    )
    (net (code "18") (name "/PA7{slash}{slash}MOSI") (class "Default")
      (node (ref "U5") (pin "3") (pinfunction "SDA_3") (pintype "passive"))
      (node (ref "U6") (pin "13") (pinfunction "PA7_13") (pintype "bidirectional"))
    )
    (net (code "19") (name "/PA8{slash}{slash}SET") (class "Default")
      (node (ref "SW2") (pin "2") (pinfunction "2_2") (pintype "passive"))
      (node (ref "U6") (pin "18") (pinfunction "PA8_18") (pintype "bidirectional"))
    )
    (net (code "20") (name "/PA9{slash}{slash}SCL") (class "Default")
      (node (ref "R22") (pin "2") (pinfunction "2_2") (pintype "passive"))
      (node (ref "R28") (pin "2") (pinfunction "2_2") (pintype "passive"))
      (node (ref "TP16") (pin "1") (pintype "passive"))
      (node (ref "U10") (pin "6") (pinfunction "SCL_6") (pintype "input"))
      (node (ref "U11") (pin "1") (pinfunction "SCL/SPC_1") (pintype "passive"))
      (node (ref "U12") (pin "2") (pinfunction "SCL_2") (pintype "input"))
      (node (ref "U2") (pin "2") (pinfunction "SCL_2") (pintype "bidirectional"))
      (node (ref "U6") (pin "19") (pinfunction "PA9_19") (pintype "bidirectional"))
      (node (ref "U7") (pin "2") (pinfunction "SCL_2") (pintype "input"))
      (node (ref "U9") (pin "3") (pinfunction "SCL_3") (pintype "input"))
    )
    (net (code "21") (name "/PA10{slash}{slash}SDA") (class "Default")
      (node (ref "R23") (pin "2") (pinfunction "2_2") (pintype "passive"))
      (node (ref "R29") (pin "2") (pinfunction "2_2") (pintype "passive"))
      (node (ref "TP15") (pin "1") (pintype "passive"))
      (node (ref "U10") (pin "5") (pinfunction "SDA_5") (pintype "bidirectional"))
      (node (ref "U11") (pin "4") (pinfunction "SDA/SDI/SDO_4") (pintype "passive"))
      (node (ref "U12") (pin "1") (pinfunction "SDA_1") (pintype "bidirectional"))
      (node (ref "U2") (pin "1") (pinfunction "SDA_1") (pintype "bidirectional"))
      (node (ref "U6") (pin "20") (pinfunction "PA10_20") (pintype "bidirectional"))
      (node (ref "U7") (pin "3") (pinfunction "SDA_3") (pintype "bidirectional"))
      (node (ref "U9") (pin "4") (pinfunction "SDA_4") (pintype "bidirectional"))
    )
    (net (code "22") (name "/PA11{slash}{slash}DEBUG") (class "Default")
      (node (ref "SW3") (pin "2") (pinfunction "2_2") (pintype "passive"))
      (node (ref "U6") (pin "21") (pinfunction "PA11_21") (pintype "bidirectional"))
    )
    (net (code "23") (name "/PA12{slash}{slash}IND_ENA") (class "Default")
      (node (ref "SW4") (pin "COM") (pinfunction "COM_COM") (pintype "passive"))
      (node (ref "U6") (pin "22") (pinfunction "PA12_22") (pintype "bidirectional"))
    )
    (net (code "24") (name "/PA15{slash}{slash}JTDI{slash}{slash}GPOUT") (class "Default")
      (node (ref "R6") (pin "1") (pinfunction "1_1") (pintype "passive"))
      (node (ref "U2") (pin "12") (pinfunction "GPOUT_12") (pintype "output"))
      (node (ref "U6") (pin "25") (pinfunction "PA15_25") (pintype "bidirectional"))
    )
    (net (code "25") (name "/PB0{slash}{slash}IND_CTRL") (class "Default")
      (node (ref "Q5") (pin "1") (pinfunction "G_1") (pintype "passive"))
      (node (ref "R31") (pin "2") (pinfunction "2_2") (pintype "passive"))
      (node (ref "U6") (pin "14") (pinfunction "PB0_14") (pintype "bidirectional"))
    )
    (net (code "26") (name "/PB1{slash}{slash}STOR_CLK") (class "Default")
      (node (ref "U4") (pin "12") (pinfunction "STCP_12") (pintype "input"))
      (node (ref "U6") (pin "15") (pinfunction "PB1_15") (pintype "bidirectional"))
    )
    (net (code "27") (name "/PB3{slash}{slash}JTDO{slash}{slash}RES") (class "Default")
      (node (ref "U5") (pin "6") (pinfunction "RES_6") (pintype "passive"))
      (node (ref "U6") (pin "26") (pinfunction "PB3_26") (pintype "bidirectional"))
    )
    (net (code "28") (name "/PB4{slash}{slash}NJTRST{slash}{slash}DC") (class "Default")
      (node (ref "U5") (pin "5") (pinfunction "RS_5") (pintype "passive"))
      (node (ref "U6") (pin "27") (pinfunction "PB4_27") (pintype "bidirectional"))
    )
    (net (code "29") (name "/PB5{slash}{slash}DIN") (class "Default")
      (node (ref "TP7") (pin "1") (pintype "passive"))
      (node (ref "U4") (pin "14") (pinfunction "DS_14") (pintype "input"))
      (node (ref "U6") (pin "28") (pinfunction "PB5_28") (pintype "bidirectional"))
    )
    (net (code "30") (name "/PB6{slash}{slash}CLK") (class "Default")
      (node (ref "TP8") (pin "1") (pintype "passive"))
      (node (ref "U4") (pin "11") (pinfunction "SHCP_11") (pintype "input"))
      (node (ref "U6") (pin "29") (pinfunction "PB6_29") (pintype "bidirectional"))
    )
    (net (code "31") (name "/PB7{slash}{slash}OE_CTRL") (class "Default")
      (node (ref "D9") (pin "2") (pinfunction "A_2") (pintype "passive"))
      (node (ref "R18") (pin "1") (pinfunction "1_1") (pintype "passive"))
      (node (ref "TP9") (pin "1") (pintype "passive"))
      (node (ref "U6") (pin "30") (pinfunction "PB7_30") (pintype "bidirectional"))
    )
    (net (code "32") (name "/PROG") (class "Default")
      (node (ref "R2") (pin "1") (pinfunction "1_1") (pintype "passive"))
      (node (ref "U1") (pin "5") (pinfunction "PROG_5") (pintype "passive"))
    )
    (net (code "33") (name "/RST") (class "Default")
      (node (ref "C14") (pin "2") (pinfunction "2_2") (pintype "passive"))
      (node (ref "P1") (pin "1") (pinfunction "1_1") (pintype "passive"))
      (node (ref "R21") (pin "1") (pinfunction "1_1") (pintype "passive"))
      (node (ref "S1") (pin "2") (pinfunction "2_2") (pintype "passive"))
      (node (ref "U6") (pin "4") (pinfunction "~{RST}_4") (pintype "input"))
    )
    (net (code "34") (name "/STAT") (class "Default")
      (node (ref "R3") (pin "2") (pinfunction "2_2") (pintype "passive"))
      (node (ref "U1") (pin "1") (pinfunction "STAT_1") (pintype "passive"))
    )
    (net (code "35") (name "/SWCLK") (class "Default")
      (node (ref "P1") (pin "3") (pinfunction "3_3") (pintype "passive"))
      (node (ref "U6") (pin "24") (pinfunction "PA14_24") (pintype "bidirectional"))
    )
    (net (code "36") (name "/SWDIO") (class "Default")
      (node (ref "P1") (pin "2") (pinfunction "2_2") (pintype "passive"))
      (node (ref "U6") (pin "23") (pinfunction "PA13_23") (pintype "bidirectional"))
    )
    (net (code "37") (name "/TP0") (class "Default")
      (node (ref "U5") (pin "1") (pinfunction "TP0_1") (pintype "passive+no_connect"))
    )
    (net (code "38") (name "/TP1") (class "Default")
      (node (ref "U5") (pin "2") (pinfunction "TP1_2") (pintype "passive+no_connect"))
    )
    (net (code "39") (name "/VBACKUP") (class "Default")
      (node (ref "R33") (pin "2") (pinfunction "2_2") (pintype "passive"))
      (node (ref "U9") (pin "6") (pinfunction "VBACKUP_6") (pintype "power_in"))
    )
    (net (code "40") (name "/VSYS_GATE") (class "Default")
      (node (ref "D3") (pin "1") (pinfunction "C_1") (pintype "passive"))
      (node (ref "Q1") (pin "1") (pinfunction "G_1") (pintype "passive"))
      (node (ref "R5") (pin "1") (pinfunction "1_1") (pintype "passive"))
    )
    (net (code "41") (name "1V8") (class "Default")
      (node (ref "C15") (pin "1") (pinfunction "1_1") (pintype "passive"))
      (node (ref "C16") (pin "1") (pinfunction "1_1") (pintype "passive"))
      (node (ref "C20") (pin "2") (pinfunction "2_2") (pintype "passive"))
      (node (ref "R27") (pin "2") (pinfunction "2_2") (pintype "passive"))
      (node (ref "U7") (pin "11") (pinfunction "VDD_11") (pintype "power_in"))
      (node (ref "U8") (pin "5") (pinfunction "OUT_5") (pintype "power_in"))
    )
    (net (code "42") (name "3V3") (class "Default")
      (node (ref "C10") (pin "1") (pinfunction "1_1") (pintype "passive"))
      (node (ref "C11") (pin "1") (pinfunction "1_1") (pintype "passive"))
      (node (ref "C12") (pin "1") (pinfunction "1_1") (pintype "passive"))
      (node (ref "C13") (pin "1") (pinfunction "1_1") (pintype "passive"))
      (node (ref "C17") (pin "1") (pinfunction "1_1") (pintype "passive"))
      (node (ref "C18") (pin "1") (pinfunction "1_1") (pintype "passive"))
      (node (ref "C19") (pin "2") (pinfunction "2_2") (pintype "passive"))
      (node (ref "C21") (pin "1") (pinfunction "1_1") (pintype "passive"))
      (node (ref "C22") (pin "1") (pinfunction "1_1") (pintype "passive"))
      (node (ref "C23") (pin "1") (pinfunction "1_1") (pintype "passive"))
      (node (ref "C24") (pin "1") (pinfunction "1_1") (pintype "passive"))
      (node (ref "C25") (pin "1") (pinfunction "1_1") (pintype "passive"))
      (node (ref "C5") (pin "1") (pinfunction "1_1") (pintype "passive"))
      (node (ref "C7") (pin "1") (pinfunction "1_1") (pintype "passive"))
      (node (ref "C8") (pin "1") (pinfunction "1_1") (pintype "passive"))
      (node (ref "C9") (pin "1") (pinfunction "1_1") (pintype "passive"))
      (node (ref "D12") (pin "2") (pinfunction "A_2") (pintype "passive"))
      (node (ref "R14") (pin "2") (pinfunction "2_2") (pintype "passive"))
      (node (ref "R16") (pin "1") (pinfunction "1_1") (pintype "passive"))
      (node (ref "R21") (pin "2") (pinfunction "2_2") (pintype "passive"))
      (node (ref "R22") (pin "1") (pinfunction "1_1") (pintype "passive"))
      (node (ref "R23") (pin "1") (pinfunction "1_1") (pintype "passive"))
      (node (ref "R32") (pin "2") (pinfunction "2_2") (pintype "passive"))
      (node (ref "R39") (pin "2") (pinfunction "2_2") (pintype "passive"))
      (node (ref "R6") (pin "2") (pinfunction "2_2") (pintype "passive"))
      (node (ref "TP17") (pin "1") (pintype "passive"))
      (node (ref "U10") (pin "8") (pinfunction "VCC_8") (pintype "power_in"))
      (node (ref "U11") (pin "10") (pinfunction "VDD_IO_10") (pintype "power_in"))
      (node (ref "U11") (pin "2") (pinfunction "CS_2") (pintype "passive"))
      (node (ref "U11") (pin "9") (pinfunction "VDD_9") (pintype "power_in"))
      (node (ref "U12") (pin "5") (pinfunction "A2_5") (pintype "input"))
      (node (ref "U12") (pin "6") (pinfunction "A1_6") (pintype "input"))
      (node (ref "U12") (pin "7") (pinfunction "A0_7") (pintype "input"))
      (node (ref "U12") (pin "8") (pinfunction "VDD_8") (pintype "power_in"))
      (node (ref "U3") (pin "5") (pinfunction "VOUT_5") (pintype "passive"))
      (node (ref "U4") (pin "10") (pinfunction "~{MR}_10") (pintype "input"))
      (node (ref "U4") (pin "16") (pinfunction "VCC_16") (pintype "power_in"))
      (node (ref "U5") (pin "10") (pinfunction "VCC_10") (pintype "passive"))
      (node (ref "U5") (pin "12") (pinfunction "LEDA_12") (pintype "passive"))
      (node (ref "U6") (pin "1") (pinfunction "VDD_1") (pintype "power_in"))
      (node (ref "U6") (pin "17") (pinfunction "VDD_17") (pintype "power_in"))
      (node (ref "U6") (pin "5") (pinfunction "VDDA/VREF+_5") (pintype "power_in"))
      (node (ref "U7") (pin "10") (pinfunction "VLED+_10") (pintype "output"))
      (node (ref "U7") (pin "9") (pinfunction "VLED+_9") (pintype "output"))
      (node (ref "U8") (pin "1") (pinfunction "IN_1") (pintype "power_in"))
      (node (ref "U8") (pin "3") (pinfunction "EN_3") (pintype "input"))
      (node (ref "U9") (pin "7") (pinfunction "VDD_7") (pintype "power_in"))
    )
    (net (code "43") (name "GND") (class "Default")
      (node (ref "C1") (pin "1") (pinfunction "1_1") (pintype "passive"))
      (node (ref "C10") (pin "2") (pinfunction "2_2") (pintype "passive"))
      (node (ref "C11") (pin "2") (pinfunction "2_2") (pintype "passive"))
      (node (ref "C12") (pin "2") (pinfunction "2_2") (pintype "passive"))
      (node (ref "C13") (pin "2") (pinfunction "2_2") (pintype "passive"))
      (node (ref "C14") (pin "1") (pinfunction "1_1") (pintype "passive"))
      (node (ref "C15") (pin "2") (pinfunction "2_2") (pintype "passive"))
      (node (ref "C16") (pin "2") (pinfunction "2_2") (pintype "passive"))
      (node (ref "C17") (pin "2") (pinfunction "2_2") (pintype "passive"))
      (node (ref "C18") (pin "2") (pinfunction "2_2") (pintype "passive"))
      (node (ref "C19") (pin "1") (pinfunction "1_1") (pintype "passive"))
      (node (ref "C2") (pin "2") (pinfunction "2_2") (pintype "passive"))
      (node (ref "C20") (pin "1") (pinfunction "1_1") (pintype "passive"))
      (node (ref "C21") (pin "2") (pinfunction "2_2") (pintype "passive"))
      (node (ref "C22") (pin "2") (pinfunction "2_2") (pintype "passive"))
      (node (ref "C23") (pin "2") (pinfunction "2_2") (pintype "passive"))
      (node (ref "C24") (pin "2") (pinfunction "2_2") (pintype "passive"))
      (node (ref "C25") (pin "2") (pinfunction "2_2") (pintype "passive"))
      (node (ref "C3") (pin "2") (pinfunction "2_2") (pintype "passive"))
      (node (ref "C4") (pin "1") (pinfunction "1_1") (pintype "passive"))
      (node (ref "C5") (pin "2") (pinfunction "2_2") (pintype "passive"))
      (node (ref "C6") (pin "2") (pinfunction "2_2") (pintype "passive"))
      (node (ref "C7") (pin "2") (pinfunction "2_2") (pintype "passive"))
      (node (ref "C8") (pin "2") (pinfunction "2_2") (pintype "passive"))
      (node (ref "C9") (pin "2") (pinfunction "2_2") (pintype "passive"))
      (node (ref "D4") (pin "1") (pinfunction "C_1") (pintype "passive"))
      (node (ref "D5") (pin "1") (pinfunction "C_1") (pintype "passive"))
      (node (ref "D6") (pin "1") (pinfunction "C_1") (pintype "passive"))
      (node (ref "D7") (pin "1") (pinfunction "C_1") (pintype "passive"))
      (node (ref "J1") (pin "1") (pinfunction "MNT_1_1") (pintype "power_in"))
      (node (ref "J1") (pin "2") (pinfunction "MNT_2_2") (pintype "power_in"))
      (node (ref "J1") (pin "3") (pinfunction "MNT_3_3") (pintype "power_in"))
      (node (ref "J1") (pin "4") (pinfunction "MNT_4_4") (pintype "power_in"))
      (node (ref "J1") (pin "A1-B12") (pinfunction "GND_A1-B12") (pintype "power_in"))
      (node (ref "J1") (pin "B1-A12") (pinfunction "GND_B1-A12") (pintype "bidirectional"))
      (node (ref "J2") (pin "1") (pinfunction "1_1") (pintype "passive"))
      (node (ref "P1") (pin "4") (pinfunction "4_4") (pintype "passive"))
      (node (ref "P2") (pin "4") (pinfunction "4_4") (pintype "passive"))
      (node (ref "Q2") (pin "2") (pinfunction "E_2") (pintype "passive"))
      (node (ref "Q3") (pin "2") (pinfunction "S_2") (pintype "passive"))
      (node (ref "Q4") (pin "2") (pinfunction "S_2") (pintype "passive"))
      (node (ref "Q5") (pin "2") (pinfunction "S_2") (pintype "passive"))
      (node (ref "R1") (pin "1") (pinfunction "1_1") (pintype "passive"))
      (node (ref "R18") (pin "2") (pinfunction "2_2") (pintype "passive"))
      (node (ref "R19") (pin "1") (pinfunction "1_1") (pintype "passive"))
      (node (ref "R2") (pin "2") (pinfunction "2_2") (pintype "passive"))
      (node (ref "R20") (pin "1") (pinfunction "1_1") (pintype "passive"))
      (node (ref "R24") (pin "1") (pinfunction "1_1") (pintype "passive"))
      (node (ref "R25") (pin "1") (pinfunction "1_1") (pintype "passive"))
      (node (ref "R28") (pin "1") (pinfunction "1_1") (pintype "passive"))
      (node (ref "R29") (pin "1") (pinfunction "1_1") (pintype "passive"))
      (node (ref "R31") (pin "1") (pinfunction "1_1") (pintype "passive"))
      (node (ref "R33") (pin "1") (pinfunction "1_1") (pintype "passive"))
      (node (ref "R34") (pin "1") (pinfunction "1_1") (pintype "passive"))
      (node (ref "R35") (pin "1") (pinfunction "1_1") (pintype "passive"))
      (node (ref "R36") (pin "1") (pinfunction "1_1") (pintype "passive"))
      (node (ref "R37") (pin "1") (pinfunction "1_1") (pintype "passive"))
      (node (ref "R38") (pin "1") (pinfunction "1_1") (pintype "passive"))
      (node (ref "R5") (pin "2") (pinfunction "2_2") (pintype "passive"))
      (node (ref "R7") (pin "1") (pinfunction "1_1") (pintype "passive"))
      (node (ref "R8") (pin "1") (pinfunction "1_1") (pintype "passive"))
      (node (ref "S1") (pin "1") (pinfunction "1_1") (pintype "passive"))
      (node (ref "SW2") (pin "1") (pinfunction "1_1") (pintype "passive"))
      (node (ref "SW3") (pin "1") (pinfunction "1_1") (pintype "passive"))
      (node (ref "SW4") (pin "L2") (pinfunction "L2_L2") (pintype "passive"))
      (node (ref "SW5") (pin "1") (pinfunction "1_1") (pintype "passive"))
      (node (ref "TP11") (pin "1") (pintype "passive"))
      (node (ref "TP12") (pin "1") (pintype "passive"))
      (node (ref "TP13") (pin "1") (pintype "passive"))
      (node (ref "U1") (pin "2") (pinfunction "VSS_2") (pintype "power_in"))
      (node (ref "U10") (pin "4") (pinfunction "VSS_4") (pintype "power_in"))
      (node (ref "U11") (pin "3") (pinfunction "SDO/SA0_3") (pintype "passive"))
      (node (ref "U11") (pin "6") (pinfunction "GND_6") (pintype "power_in"))
      (node (ref "U11") (pin "7") (pinfunction "RES_7") (pintype "passive"))
      (node (ref "U11") (pin "8") (pinfunction "GND_8") (pintype "power_in"))
      (node (ref "U12") (pin "4") (pinfunction "GND_4") (pintype "power_in"))
      (node (ref "U12") (pin "9") (pinfunction "EP_9") (pintype "power_in"))
      (node (ref "U2") (pin "13") (pinfunction "EP_13") (pintype "power_in"))
      (node (ref "U2") (pin "3") (pinfunction "VSS_3") (pintype "power_in"))
      (node (ref "U3") (pin "2") (pinfunction "VSS_2") (pintype "passive"))
      (node (ref "U4") (pin "8") (pinfunction "GND_8") (pintype "power_in"))
      (node (ref "U5") (pin "13") (pinfunction "GND_13") (pintype "passive"))
      (node (ref "U5") (pin "8") (pinfunction "GND_8") (pintype "passive"))
      (node (ref "U6") (pin "16") (pinfunction "VSS_16") (pintype "power_in"))
      (node (ref "U6") (pin "32") (pinfunction "VSS_32") (pintype "power_in"))
      (node (ref "U6") (pin "33") (pinfunction "EP_33") (pintype "power_in"))
      (node (ref "U7") (pin "12") (pinfunction "GND_12") (pintype "power_in"))
      (node (ref "U7") (pin "4") (pinfunction "PGND_4") (pintype "power_in"))
      (node (ref "U8") (pin "2") (pinfunction "GND_2") (pintype "power_in"))
      (node (ref "U9") (pin "5") (pinfunction "VSS_5") (pintype "power_in"))
    )
    (net (code "44") (name "LDO_IN") (class "Default")
      (node (ref "C6") (pin "1") (pinfunction "1_1") (pintype "passive"))
      (node (ref "D2") (pin "1") (pinfunction "C_1") (pintype "passive"))
      (node (ref "Q1") (pin "2") (pinfunction "S_2") (pintype "passive"))
      (node (ref "TP2") (pin "1") (pintype "passive"))
      (node (ref "U3") (pin "1") (pinfunction "VIN_1") (pintype "passive"))
    )
    (net (code "45") (name "Net-(D1-C)") (class "Default")
      (node (ref "D1") (pin "1") (pinfunction "C_1") (pintype "passive"))
      (node (ref "R3") (pin "1") (pinfunction "1_1") (pintype "passive"))
    )
    (net (code "46") (name "Net-(D4-A)") (class "Default")
      (node (ref "D4") (pin "2") (pinfunction "A_2") (pintype "passive"))
      (node (ref "R9") (pin "1") (pinfunction "1_1") (pintype "passive"))
    )
    (net (code "47") (name "Net-(D5-A)") (class "Default")
      (node (ref "D5") (pin "2") (pinfunction "A_2") (pintype "passive"))
      (node (ref "R10") (pin "1") (pinfunction "1_1") (pintype "passive"))
    )
    (net (code "48") (name "Net-(D6-A)") (class "Default")
      (node (ref "D6") (pin "2") (pinfunction "A_2") (pintype "passive"))
      (node (ref "R11") (pin "1") (pinfunction "1_1") (pintype "passive"))
    )
    (net (code "49") (name "Net-(D7-A)") (class "Default")
      (node (ref "D7") (pin "2") (pinfunction "A_2") (pintype "passive"))
      (node (ref "R12") (pin "1") (pinfunction "1_1") (pintype "passive"))
    )
    (net (code "50") (name "Net-(D8-C)") (class "Default")
      (node (ref "D8") (pin "1") (pinfunction "C_1") (pintype "passive"))
      (node (ref "Q3") (pin "1") (pinfunction "G_1") (pintype "passive"))
      (node (ref "R19") (pin "2") (pinfunction "2_2") (pintype "passive"))
    )
    (net (code "51") (name "Net-(D9-C)") (class "Default")
      (node (ref "D9") (pin "1") (pinfunction "C_1") (pintype "passive"))
      (node (ref "Q4") (pin "1") (pinfunction "G_1") (pintype "passive"))
      (node (ref "R20") (pin "2") (pinfunction "2_2") (pintype "passive"))
    )
    (net (code "52") (name "Net-(D10-C)") (class "Default")
      (node (ref "D10") (pin "1") (pinfunction "C_1") (pintype "passive"))
      (node (ref "R25") (pin "2") (pinfunction "2_2") (pintype "passive"))
    )
    (net (code "53") (name "Net-(D11-C)") (class "Default")
      (node (ref "D11") (pin "1") (pinfunction "C_1") (pintype "passive"))
      (node (ref "R26") (pin "2") (pinfunction "2_2") (pintype "passive"))
    )
    (net (code "54") (name "Net-(D12-C)") (class "Default")
      (node (ref "D12") (pin "1") (pinfunction "C_1") (pintype "passive"))
      (node (ref "R30") (pin "2") (pinfunction "2_2") (pintype "passive"))
    )
    (net (code "55") (name "Net-(J1-CC1)") (class "Default")
      (node (ref "J1") (pin "A5") (pinfunction "CC1_A5") (pintype "power_in"))
      (node (ref "R1") (pin "2") (pinfunction "2_2") (pintype "passive"))
    )
    (net (code "56") (name "Net-(J1-CC2)") (class "Default")
      (node (ref "J1") (pin "B5") (pinfunction "CC2_B5") (pintype "bidirectional"))
      (node (ref "R7") (pin "2") (pinfunction "2_2") (pintype "passive"))
    )
    (net (code "57") (name "Net-(Q1-D)") (class "Default")
      (node (ref "Q1") (pin "3") (pinfunction "D_3") (pintype "passive"))
      (node (ref "SW1") (pin "L1") (pinfunction "L1_L1") (pintype "passive"))
    )
    (net (code "58") (name "Net-(Q5-D)") (class "Default")
      (node (ref "Q5") (pin "3") (pinfunction "D_3") (pintype "passive"))
      (node (ref "R26") (pin "1") (pinfunction "1_1") (pintype "passive"))
      (node (ref "R30") (pin "1") (pinfunction "1_1") (pintype "passive"))
    )
    (net (code "59") (name "Net-(U4-Q0)") (class "Default")
      (node (ref "R9") (pin "2") (pinfunction "2_2") (pintype "passive"))
      (node (ref "U4") (pin "15") (pinfunction "Q0_15") (pintype "output"))
    )
    (net (code "60") (name "Net-(U4-Q1)") (class "Default")
      (node (ref "R10") (pin "2") (pinfunction "2_2") (pintype "passive"))
      (node (ref "U4") (pin "1") (pinfunction "Q1_1") (pintype "output"))
    )
    (net (code "61") (name "Net-(U4-Q2)") (class "Default")
      (node (ref "R11") (pin "2") (pinfunction "2_2") (pintype "passive"))
      (node (ref "U4") (pin "2") (pinfunction "Q2_2") (pintype "output"))
    )
    (net (code "62") (name "Net-(U4-Q3)") (class "Default")
      (node (ref "R12") (pin "2") (pinfunction "2_2") (pintype "passive"))
      (node (ref "U4") (pin "3") (pinfunction "Q3_3") (pintype "output"))
    )
    (net (code "63") (name "Net-(U7-~{INT})") (class "Default")
      (node (ref "R27") (pin "1") (pinfunction "1_1") (pintype "passive"))
      (node (ref "U7") (pin "13") (pinfunction "~{INT}_13") (pintype "input"))
    )
    (net (code "64") (name "Net-(U10-A0)") (class "Default")
      (node (ref "R38") (pin "2") (pinfunction "2_2") (pintype "passive"))
      (node (ref "TP20") (pin "1") (pintype "passive"))
      (node (ref "U10") (pin "1") (pinfunction "A0_1") (pintype "input"))
    )
    (net (code "65") (name "Net-(U10-A1)") (class "Default")
      (node (ref "R37") (pin "2") (pinfunction "2_2") (pintype "passive"))
      (node (ref "TP19") (pin "1") (pintype "passive"))
      (node (ref "U10") (pin "2") (pinfunction "A1_2") (pintype "input"))
    )
    (net (code "66") (name "Net-(U10-A2)") (class "Default")
      (node (ref "R36") (pin "2") (pinfunction "2_2") (pintype "passive"))
      (node (ref "TP18") (pin "1") (pintype "passive"))
      (node (ref "U10") (pin "3") (pinfunction "A2_3") (pintype "input"))
    )
    (net (code "67") (name "Net-(U10-WP)") (class "Default")
      (node (ref "R32") (pin "1") (pinfunction "1_1") (pintype "passive"))
      (node (ref "R35") (pin "2") (pinfunction "2_2") (pintype "passive"))
      (node (ref "TP21") (pin "1") (pintype "passive"))
      (node (ref "U10") (pin "7") (pinfunction "WP_7") (pintype "input"))
    )
    (net (code "68") (name "PACK+") (class "Default")
      (node (ref "C2") (pin "1") (pinfunction "1_1") (pintype "passive"))
      (node (ref "J2") (pin "2") (pinfunction "2_2") (pintype "passive"))
      (node (ref "R4") (pin "2") (pinfunction "2_2") (pintype "passive"))
      (node (ref "TP1") (pin "1") (pintype "passive"))
      (node (ref "TP5") (pin "1") (pintype "passive"))
      (node (ref "U2") (pin "6") (pinfunction "BAT_6") (pintype "input"))
      (node (ref "U2") (pin "8") (pinfunction "SRP_8") (pintype "input"))
    )
    (net (code "69") (name "USB_VCC") (class "Default")
      (node (ref "C1") (pin "2") (pinfunction "2_2") (pintype "passive"))
      (node (ref "D1") (pin "2") (pinfunction "A_2") (pintype "passive"))
      (node (ref "D10") (pin "2") (pinfunction "A_2") (pintype "passive"))
      (node (ref "D2") (pin "2") (pinfunction "A_2") (pintype "passive"))
      (node (ref "D3") (pin "2") (pinfunction "A_2") (pintype "passive"))
      (node (ref "D8") (pin "2") (pinfunction "A_2") (pintype "passive"))
      (node (ref "J1") (pin "A4-B9") (pinfunction "VBUS_A4-B9") (pintype "power_in"))
      (node (ref "J1") (pin "B4-A9") (pinfunction "VBUS_B4-A9") (pintype "bidirectional"))
      (node (ref "TP14") (pin "1") (pintype "passive"))
      (node (ref "U1") (pin "4") (pinfunction "VDD_4") (pintype "power_in"))
    )
    (net (code "70") (name "VDD") (class "Default")
      (node (ref "C3") (pin "1") (pinfunction "1_1") (pintype "passive"))
      (node (ref "U2") (pin "5") (pinfunction "VDD_5") (pintype "power_in"))
    )
    (net (code "71") (name "VSYS") (class "Default")
      (node (ref "C4") (pin "2") (pinfunction "2_2") (pintype "passive"))
      (node (ref "R4") (pin "1") (pinfunction "1_1") (pintype "passive"))
      (node (ref "SW1") (pin "COM") (pinfunction "COM_COM") (pintype "passive"))
      (node (ref "TP3") (pin "1") (pintype "passive"))
      (node (ref "TP4") (pin "1") (pintype "passive"))
      (node (ref "U1") (pin "3") (pinfunction "VBAT_3") (pintype "power_in"))
      (node (ref "U2") (pin "7") (pinfunction "SRN_7") (pintype "input"))
    )
    (net (code "72") (name "unconnected-(J1-Dn1-PadA7)") (class "Default")
      (node (ref "J1") (pin "A7") (pinfunction "Dn1_A7") (pintype "bidirectional+no_connect"))
    )
    (net (code "73") (name "unconnected-(J1-Dn2-PadB7)") (class "Default")
      (node (ref "J1") (pin "B7") (pinfunction "Dn2_B7") (pintype "bidirectional+no_connect"))
    )
    (net (code "74") (name "unconnected-(J1-Dp1-PadA6)") (class "Default")
      (node (ref "J1") (pin "A6") (pinfunction "Dp1_A6") (pintype "bidirectional+no_connect"))
    )
    (net (code "75") (name "unconnected-(J1-Dp2-PadB6)") (class "Default")
      (node (ref "J1") (pin "B6") (pinfunction "Dp2_B6") (pintype "bidirectional+no_connect"))
    )
    (net (code "76") (name "unconnected-(J1-SBU1-PadA8)") (class "Default")
      (node (ref "J1") (pin "A8") (pinfunction "SBU1_A8") (pintype "bidirectional+no_connect"))
    )
    (net (code "77") (name "unconnected-(J1-SBU2-PadB8)") (class "Default")
      (node (ref "J1") (pin "B8") (pinfunction "SBU2_B8") (pintype "power_in+no_connect"))
    )
    (net (code "78") (name "unconnected-(P2-Pad2)") (class "Default")
      (node (ref "P2") (pin "2") (pinfunction "2_2") (pintype "passive+no_connect"))
    )
    (net (code "79") (name "unconnected-(SW1-PadL2)") (class "Default")
      (node (ref "SW1") (pin "L2") (pinfunction "L2_L2") (pintype "passive+no_connect"))
    )
    (net (code "80") (name "unconnected-(SW4-PadL1)") (class "Default")
      (node (ref "SW4") (pin "L1") (pinfunction "L1_L1") (pintype "passive+no_connect"))
    )
    (net (code "81") (name "unconnected-(U2-NC-Pad4)") (class "Default")
      (node (ref "U2") (pin "4") (pinfunction "NC_4") (pintype "passive+no_connect"))
    )
    (net (code "82") (name "unconnected-(U2-NC-Pad9)") (class "Default")
      (node (ref "U2") (pin "9") (pinfunction "NC_9") (pintype "passive+no_connect"))
    )
    (net (code "83") (name "unconnected-(U2-NC-Pad11)") (class "Default")
      (node (ref "U2") (pin "11") (pinfunction "NC_11") (pintype "passive+no_connect"))
    )
    (net (code "84") (name "unconnected-(U3-NC-Pad3)") (class "Default")
      (node (ref "U3") (pin "3") (pinfunction "NC_3") (pintype "passive+no_connect"))
    )
    (net (code "85") (name "unconnected-(U3-NC-Pad4)") (class "Default")
      (node (ref "U3") (pin "4") (pinfunction "NC_4") (pintype "passive+no_connect"))
    )
    (net (code "86") (name "unconnected-(U4-Q4-Pad4)") (class "Default")
      (node (ref "U4") (pin "4") (pinfunction "Q4_4") (pintype "output+no_connect"))
    )
    (net (code "87") (name "unconnected-(U4-Q5-Pad5)") (class "Default")
      (node (ref "U4") (pin "5") (pinfunction "Q5_5") (pintype "output+no_connect"))
    )
    (net (code "88") (name "unconnected-(U4-Q6-Pad6)") (class "Default")
      (node (ref "U4") (pin "6") (pinfunction "Q6_6") (pintype "output+no_connect"))
    )
    (net (code "89") (name "unconnected-(U4-Q7-Pad7)") (class "Default")
      (node (ref "U4") (pin "7") (pinfunction "Q7_7") (pintype "output+no_connect"))
    )
    (net (code "90") (name "unconnected-(U4-Q7S-Pad9)") (class "Default")
      (node (ref "U4") (pin "9") (pinfunction "Q7S_9") (pintype "output+no_connect"))
    )
    (net (code "91") (name "unconnected-(U5-NC-Pad9)") (class "Default")
      (node (ref "U5") (pin "9") (pinfunction "NC_9") (pintype "passive+no_connect"))
    )
    (net (code "92") (name "unconnected-(U7-NC-Pad1)") (class "Default")
      (node (ref "U7") (pin "1") (pinfunction "NC_1") (pintype "passive+no_connect"))
    )
    (net (code "93") (name "unconnected-(U7-NC-Pad5)") (class "Default")
      (node (ref "U7") (pin "5") (pinfunction "NC_5") (pintype "passive+no_connect"))
    )
    (net (code "94") (name "unconnected-(U7-NC-Pad6)") (class "Default")
      (node (ref "U7") (pin "6") (pinfunction "NC_6") (pintype "passive+no_connect"))
    )
    (net (code "95") (name "unconnected-(U7-NC-Pad7)") (class "Default")
      (node (ref "U7") (pin "7") (pinfunction "NC_7") (pintype "passive+no_connect"))
    )
    (net (code "96") (name "unconnected-(U7-NC-Pad8)") (class "Default")
      (node (ref "U7") (pin "8") (pinfunction "NC_8") (pintype "passive+no_connect"))
    )
    (net (code "97") (name "unconnected-(U7-NC-Pad14)") (class "Default")
      (node (ref "U7") (pin "14") (pinfunction "NC_14") (pintype "passive+no_connect"))
    )
    (net (code "98") (name "unconnected-(U8-NC-Pad4)") (class "Default")
      (node (ref "U8") (pin "4") (pinfunction "NC_4") (pintype "passive+no_connect"))
    )
    (net (code "99") (name "unconnected-(U9-CLKOUT-Pad1)") (class "Default")
      (node (ref "U9") (pin "1") (pinfunction "CLKOUT_1") (pintype "output+no_connect"))
    )
    (net (code "100") (name "unconnected-(U9-~{INT}-Pad2)") (class "Default")
      (node (ref "U9") (pin "2") (pinfunction "~{INT}_2") (pintype "input+no_connect"))
    )
    (net (code "101") (name "unconnected-(U11-INT1-Pad12)") (class "Default")
      (node (ref "U11") (pin "12") (pinfunction "INT1_12") (pintype "input+no_connect"))
    )
    (net (code "102") (name "unconnected-(U11-INT2-Pad11)") (class "Default")
      (node (ref "U11") (pin "11") (pinfunction "INT2_11") (pintype "input+no_connect"))
    )
    (net (code "103") (name "unconnected-(U11-NC-Pad5)") (class "Default")
      (node (ref "U11") (pin "5") (pinfunction "NC_5") (pintype "passive+no_connect"))
    )
  )
)
